# design.net
KiCad netlist of a schematic drawn in EasyEDA Pro
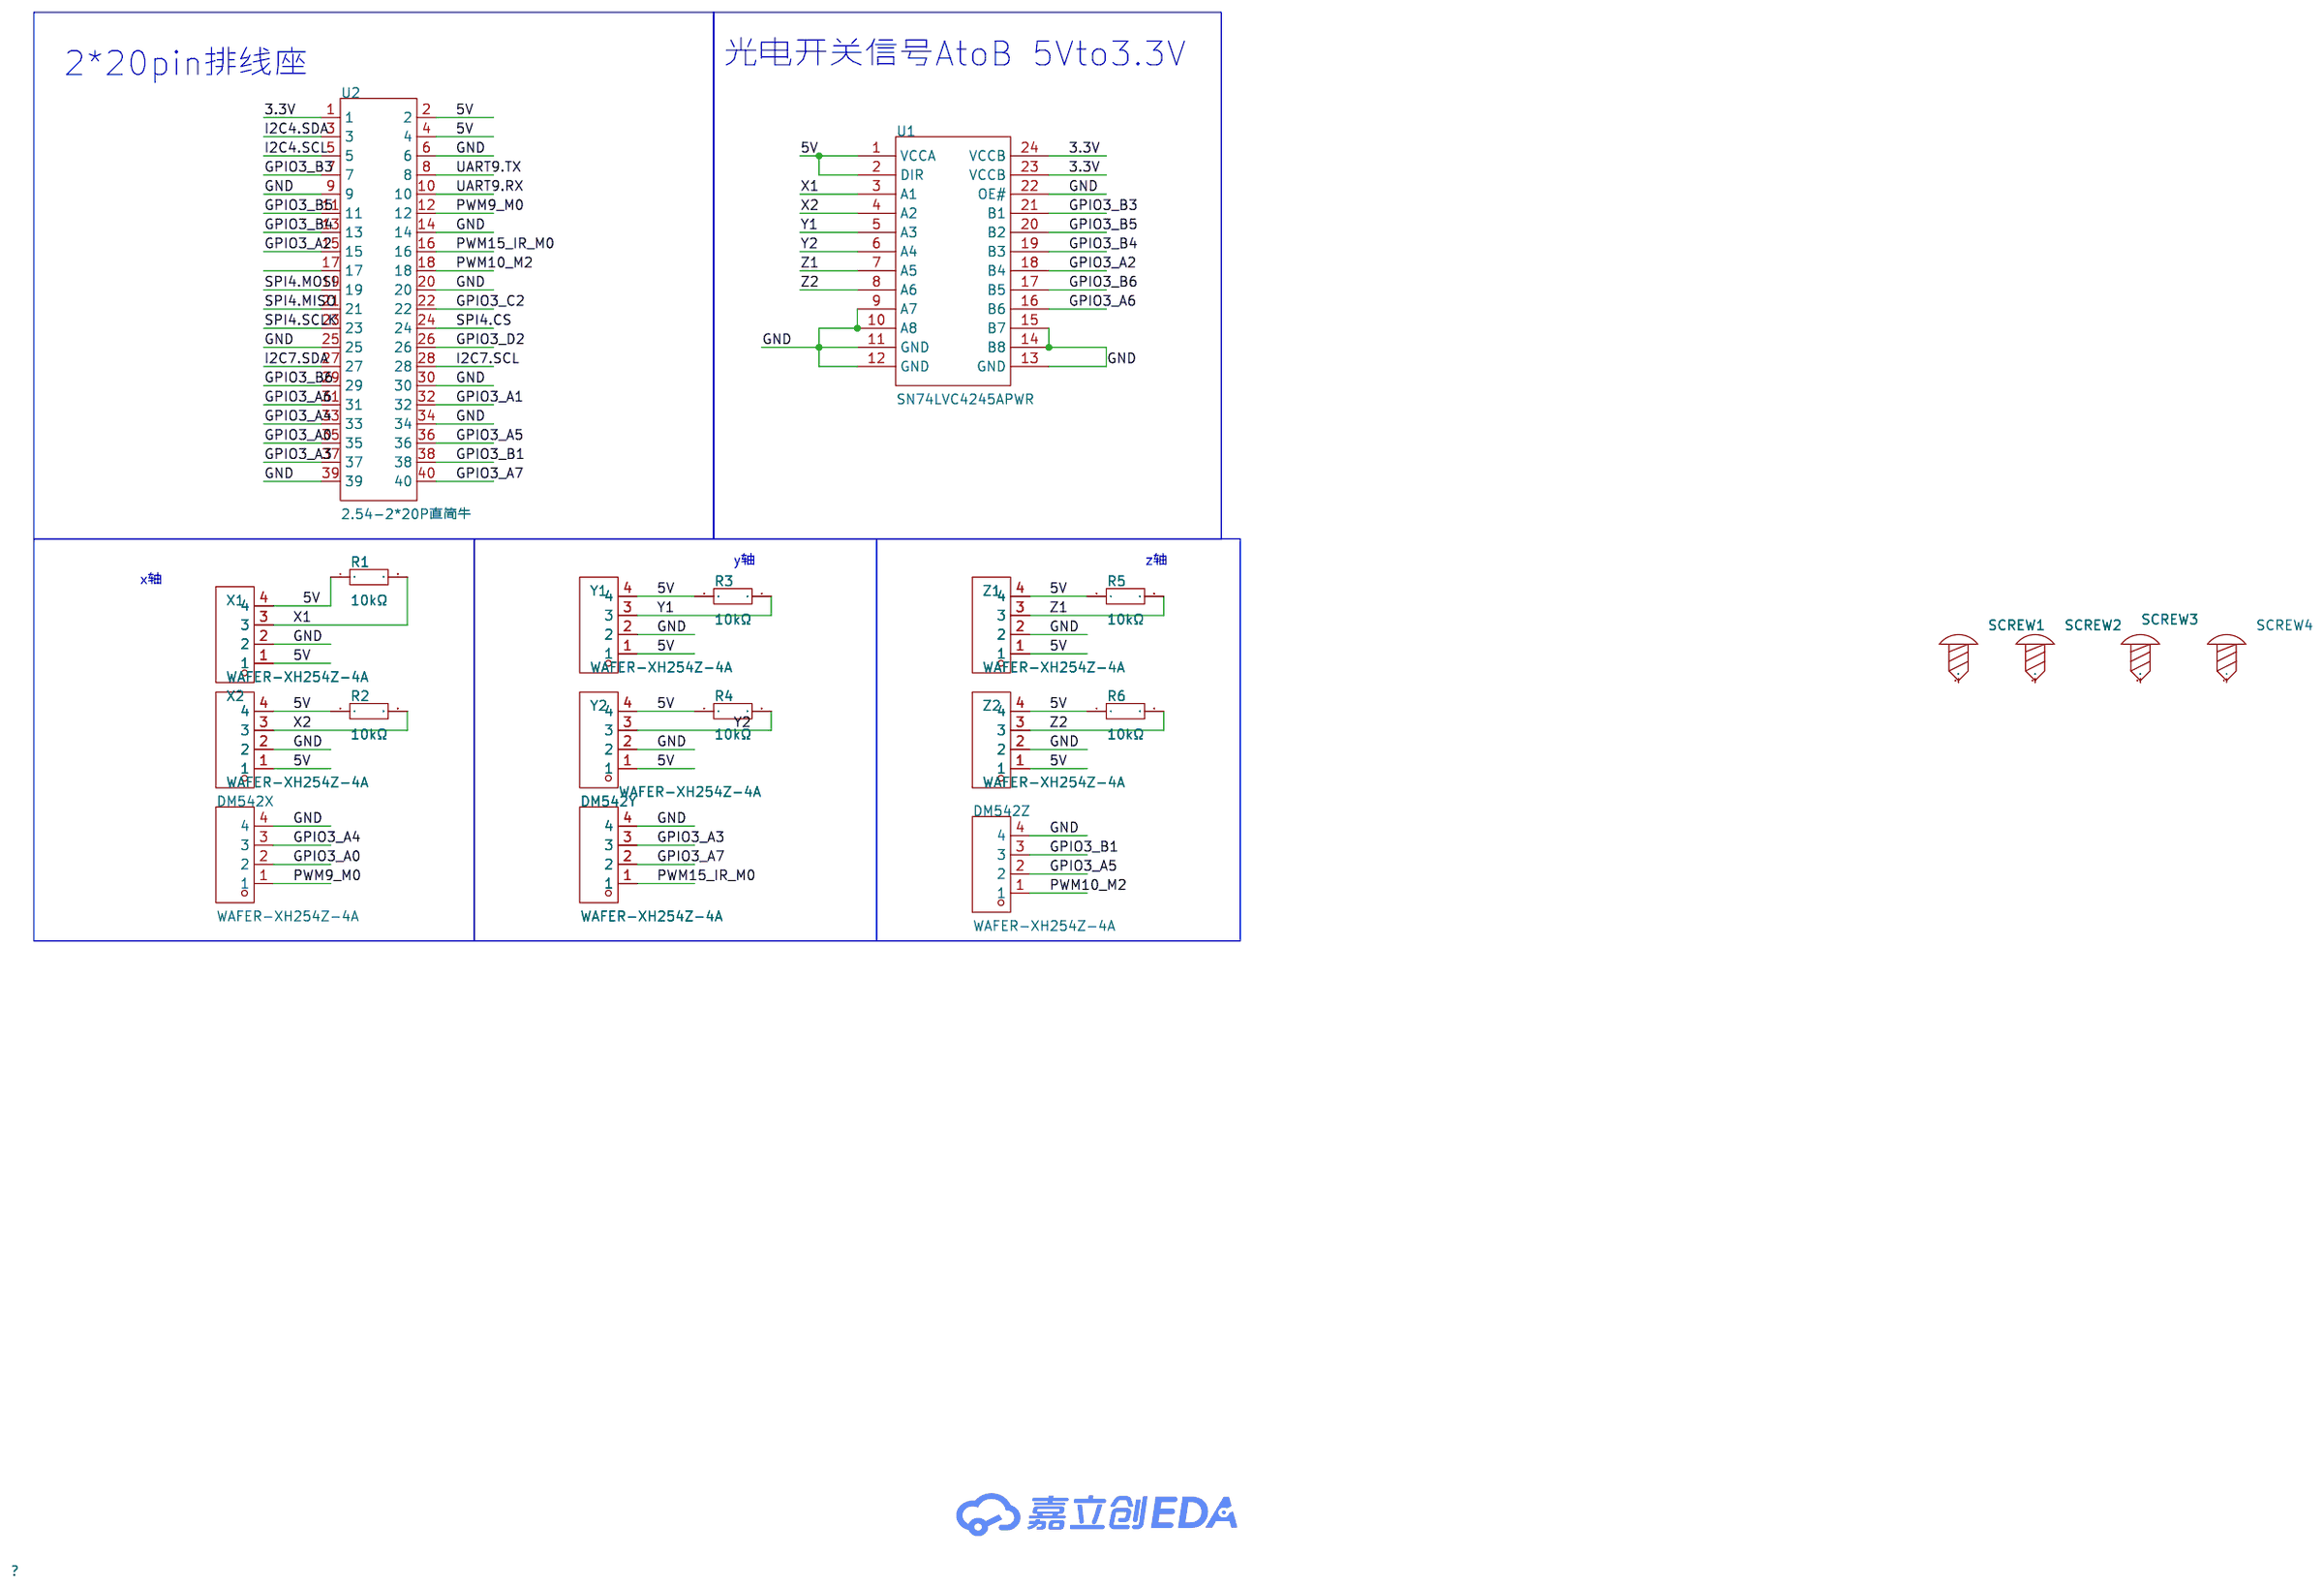
[diagram p0: schematic sheet]

(export (version "E")
  (design (tool "Eeschema 10.0.6"))
  (components
    (comp (ref "DM542X")
      (value "WAFER-XH254Z-4A")
      (footprint "easyedapro:CONN-TH_XH-4A")
      (description "插针结构:1x4P;间距:2.54mm;安装方式:直插;参考系列:XH;总PIN数:4P;排数:1;每排PIN数:4;额定电流:3A;触头材质:黄铜;工作温度:-25°C~+85°C;")
      (fields (field (name "Manufacturer") "HANBO(汉博)"))
      (libsource (lib "easyedapro") (part "WAFER-XH254Z-4A"))
    )
    (comp (ref "DM542Y")
      (value "WAFER-XH254Z-4A")
      (footprint "easyedapro:CONN-TH_XH-4A")
      (description "插针结构:1x4P;间距:2.54mm;安装方式:直插;参考系列:XH;总PIN数:4P;排数:1;每排PIN数:4;额定电流:3A;触头材质:黄铜;工作温度:-25°C~+85°C;")
      (fields (field (name "Manufacturer") "HANBO(汉博)"))
      (libsource (lib "easyedapro") (part "WAFER-XH254Z-4A"))
    )
    (comp (ref "DM542Z")
      (value "WAFER-XH254Z-4A")
      (footprint "easyedapro:CONN-TH_XH-4A")
      (description "插针结构:1x4P;间距:2.54mm;安装方式:直插;参考系列:XH;总PIN数:4P;排数:1;每排PIN数:4;额定电流:3A;触头材质:黄铜;工作温度:-25°C~+85°C;")
      (fields (field (name "Manufacturer") "HANBO(汉博)"))
      (libsource (lib "easyedapro") (part "WAFER-XH254Z-4A"))
    )
    (comp (ref "R1")
      (value "10kΩ")
      (footprint "easyedapro:R0603")
      (description "电阻类型:厚膜电阻;阻值:10kΩ;精度:±1%;功率:100mW;工作电压:75V;温度系数:±100ppm/°C;")
      (fields
        (field (name "Manufacturer Part") "0603WAF1002T5E")
        (field (name "Manufacturer") "UNI-ROYAL(厚声)")
      )
      (libsource (lib "easyedapro") (part "0603WAF1002T5E"))
    )
    (comp (ref "R2")
      (value "10kΩ")
      (footprint "easyedapro:R0603")
      (description "电阻类型:厚膜电阻;阻值:10kΩ;精度:±1%;功率:100mW;工作电压:75V;温度系数:±100ppm/°C;")
      (fields
        (field (name "Manufacturer Part") "0603WAF1002T5E")
        (field (name "Manufacturer") "UNI-ROYAL(厚声)")
      )
      (libsource (lib "easyedapro") (part "0603WAF1002T5E"))
    )
    (comp (ref "R3")
      (value "10kΩ")
      (footprint "easyedapro:R0603")
      (description "电阻类型:厚膜电阻;阻值:10kΩ;精度:±1%;功率:100mW;工作电压:75V;温度系数:±100ppm/°C;")
      (fields
        (field (name "Manufacturer Part") "0603WAF1002T5E")
        (field (name "Manufacturer") "UNI-ROYAL(厚声)")
      )
      (libsource (lib "easyedapro") (part "0603WAF1002T5E"))
    )
    (comp (ref "R4")
      (value "10kΩ")
      (footprint "easyedapro:R0603")
      (description "电阻类型:厚膜电阻;阻值:10kΩ;精度:±1%;功率:100mW;工作电压:75V;温度系数:±100ppm/°C;")
      (fields
        (field (name "Manufacturer Part") "0603WAF1002T5E")
        (field (name "Manufacturer") "UNI-ROYAL(厚声)")
      )
      (libsource (lib "easyedapro") (part "0603WAF1002T5E"))
    )
    (comp (ref "R5")
      (value "10kΩ")
      (footprint "easyedapro:R0603")
      (description "电阻类型:厚膜电阻;阻值:10kΩ;精度:±1%;功率:100mW;工作电压:75V;温度系数:±100ppm/°C;")
      (fields
        (field (name "Manufacturer Part") "0603WAF1002T5E")
        (field (name "Manufacturer") "UNI-ROYAL(厚声)")
      )
      (libsource (lib "easyedapro") (part "0603WAF1002T5E"))
    )
    (comp (ref "R6")
      (value "10kΩ")
      (footprint "easyedapro:R0603")
      (description "电阻类型:厚膜电阻;阻值:10kΩ;精度:±1%;功率:100mW;工作电压:75V;温度系数:±100ppm/°C;")
      (fields
        (field (name "Manufacturer Part") "0603WAF1002T5E")
        (field (name "Manufacturer") "UNI-ROYAL(厚声)")
      )
      (libsource (lib "easyedapro") (part "0603WAF1002T5E"))
    )
    (comp (ref "SCREW1")
      (value "~")
      (footprint "easyedapro:M3螺丝")
      (libsource (lib "easyedapro") (part "螺丝孔"))
    )
    (comp (ref "SCREW2")
      (value "~")
      (footprint "easyedapro:M3螺丝")
      (libsource (lib "easyedapro") (part "螺丝孔"))
    )
    (comp (ref "SCREW3")
      (value "~")
      (footprint "easyedapro:M3螺丝")
      (libsource (lib "easyedapro") (part "螺丝孔"))
    )
    (comp (ref "SCREW4")
      (value "~")
      (footprint "easyedapro:M3螺丝")
      (libsource (lib "easyedapro") (part "螺丝孔"))
    )
    (comp (ref "U1")
      (value "SN74LVC4245APWR")
      (footprint "easyedapro:TSSOP-24_L7.8-W4.4-P0.65-LS6.4-BL")
      (description "工作电压(VCCA):4.5V~5.5V;工作电压(VCCB):2.7V~3.6V;通道数:1;每个电路通道数:8;")
      (fields (field (name "Manufacturer") "TI(德州仪器)"))
      (libsource (lib "easyedapro") (part "SN74LVC4245APWR"))
    )
    (comp (ref "U2")
      (value "2.54-2*20P直简牛")
      (footprint "easyedapro:HDR-TH_40P-P2.54-V-M-R2-C20-S2.54")
      (description "插针结构:2x20P;间距:2.54mm;安装方式:直插;排数:双排;总PIN位数:40P;触头镀层:金;")
      (fields (field (name "Manufacturer") "BOOMELE(博穆精密)"))
      (libsource (lib "easyedapro") (part "PZ2.54-2*20"))
    )
    (comp (ref "X1")
      (value "WAFER-XH254Z-4A")
      (footprint "easyedapro:CONN-TH_XH-4A")
      (description "插针结构:1x4P;间距:2.54mm;安装方式:直插;参考系列:XH;总PIN数:4P;排数:1;每排PIN数:4;额定电流:3A;触头材质:黄铜;工作温度:-25°C~+85°C;")
      (fields (field (name "Manufacturer") "HANBO(汉博)"))
      (libsource (lib "easyedapro") (part "WAFER-XH254Z-4A"))
    )
    (comp (ref "X2")
      (value "WAFER-XH254Z-4A")
      (footprint "easyedapro:CONN-TH_XH-4A")
      (description "插针结构:1x4P;间距:2.54mm;安装方式:直插;参考系列:XH;总PIN数:4P;排数:1;每排PIN数:4;额定电流:3A;触头材质:黄铜;工作温度:-25°C~+85°C;")
      (fields (field (name "Manufacturer") "HANBO(汉博)"))
      (libsource (lib "easyedapro") (part "WAFER-XH254Z-4A"))
    )
    (comp (ref "Y1")
      (value "WAFER-XH254Z-4A")
      (footprint "easyedapro:CONN-TH_XH-4A")
      (description "插针结构:1x4P;间距:2.54mm;安装方式:直插;参考系列:XH;总PIN数:4P;排数:1;每排PIN数:4;额定电流:3A;触头材质:黄铜;工作温度:-25°C~+85°C;")
      (fields (field (name "Manufacturer") "HANBO(汉博)"))
      (libsource (lib "easyedapro") (part "WAFER-XH254Z-4A"))
    )
    (comp (ref "Y2")
      (value "WAFER-XH254Z-4A")
      (footprint "easyedapro:CONN-TH_XH-4A")
      (description "插针结构:1x4P;间距:2.54mm;安装方式:直插;参考系列:XH;总PIN数:4P;排数:1;每排PIN数:4;额定电流:3A;触头材质:黄铜;工作温度:-25°C~+85°C;")
      (fields (field (name "Manufacturer") "HANBO(汉博)"))
      (libsource (lib "easyedapro") (part "WAFER-XH254Z-4A"))
    )
    (comp (ref "Z1")
      (value "WAFER-XH254Z-4A")
      (footprint "easyedapro:CONN-TH_XH-4A")
      (description "插针结构:1x4P;间距:2.54mm;安装方式:直插;参考系列:XH;总PIN数:4P;排数:1;每排PIN数:4;额定电流:3A;触头材质:黄铜;工作温度:-25°C~+85°C;")
      (fields (field (name "Manufacturer") "HANBO(汉博)"))
      (libsource (lib "easyedapro") (part "WAFER-XH254Z-4A"))
    )
    (comp (ref "Z2")
      (value "WAFER-XH254Z-4A")
      (footprint "easyedapro:CONN-TH_XH-4A")
      (description "插针结构:1x4P;间距:2.54mm;安装方式:直插;参考系列:XH;总PIN数:4P;排数:1;每排PIN数:4;额定电流:3A;触头材质:黄铜;工作温度:-25°C~+85°C;")
      (fields (field (name "Manufacturer") "HANBO(汉博)"))
      (libsource (lib "easyedapro") (part "WAFER-XH254Z-4A"))
    )
  )
  (nets
    (net (code "1") (name "/3.3V") (class "Default")
      (node (ref "U1") (pin "23") (pinfunction "VCCB_23") (pintype "unspecified"))
      (node (ref "U1") (pin "24") (pinfunction "VCCB_24") (pintype "unspecified"))
      (node (ref "U2") (pin "1") (pinfunction "1_1") (pintype "unspecified"))
    )
    (net (code "2") (name "/5V") (class "Default")
      (node (ref "R1") (pin "1") (pinfunction "1_1") (pintype "input"))
      (node (ref "R2") (pin "1") (pinfunction "1_1") (pintype "input"))
      (node (ref "R3") (pin "1") (pinfunction "1_1") (pintype "input"))
      (node (ref "R4") (pin "1") (pinfunction "1_1") (pintype "input"))
      (node (ref "R5") (pin "1") (pinfunction "1_1") (pintype "input"))
      (node (ref "R6") (pin "1") (pinfunction "1_1") (pintype "input"))
      (node (ref "U1") (pin "1") (pinfunction "VCCA_1") (pintype "unspecified"))
      (node (ref "U1") (pin "2") (pinfunction "DIR_2") (pintype "unspecified"))
      (node (ref "U2") (pin "2") (pinfunction "2_2") (pintype "unspecified"))
      (node (ref "U2") (pin "4") (pinfunction "4_4") (pintype "unspecified"))
      (node (ref "X1") (pin "1") (pinfunction "1_1") (pintype "unspecified"))
      (node (ref "X1") (pin "4") (pinfunction "4_4") (pintype "unspecified"))
      (node (ref "X2") (pin "1") (pinfunction "1_1") (pintype "unspecified"))
      (node (ref "X2") (pin "4") (pinfunction "4_4") (pintype "unspecified"))
      (node (ref "Y1") (pin "1") (pinfunction "1_1") (pintype "unspecified"))
      (node (ref "Y1") (pin "4") (pinfunction "4_4") (pintype "unspecified"))
      (node (ref "Y2") (pin "1") (pinfunction "1_1") (pintype "unspecified"))
      (node (ref "Y2") (pin "4") (pinfunction "4_4") (pintype "unspecified"))
      (node (ref "Z1") (pin "1") (pinfunction "1_1") (pintype "unspecified"))
      (node (ref "Z1") (pin "4") (pinfunction "4_4") (pintype "unspecified"))
      (node (ref "Z2") (pin "1") (pinfunction "1_1") (pintype "unspecified"))
      (node (ref "Z2") (pin "4") (pinfunction "4_4") (pintype "unspecified"))
    )
    (net (code "3") (name "/GND") (class "Default")
      (node (ref "DM542X") (pin "4") (pinfunction "4_4") (pintype "unspecified"))
      (node (ref "DM542Y") (pin "4") (pinfunction "4_4") (pintype "unspecified"))
      (node (ref "DM542Z") (pin "4") (pinfunction "4_4") (pintype "unspecified"))
      (node (ref "U1") (pin "10") (pinfunction "A8_10") (pintype "unspecified"))
      (node (ref "U1") (pin "11") (pinfunction "GND_11") (pintype "unspecified"))
      (node (ref "U1") (pin "12") (pinfunction "GND_12") (pintype "unspecified"))
      (node (ref "U1") (pin "13") (pinfunction "GND_13") (pintype "unspecified"))
      (node (ref "U1") (pin "14") (pinfunction "B8_14") (pintype "unspecified"))
      (node (ref "U1") (pin "15") (pinfunction "B7_15") (pintype "unspecified"))
      (node (ref "U1") (pin "22") (pinfunction "OE#_22") (pintype "unspecified"))
      (node (ref "U1") (pin "9") (pinfunction "A7_9") (pintype "unspecified"))
      (node (ref "U2") (pin "14") (pinfunction "14_14") (pintype "unspecified"))
      (node (ref "U2") (pin "20") (pinfunction "20_20") (pintype "unspecified"))
      (node (ref "U2") (pin "25") (pinfunction "25_25") (pintype "unspecified"))
      (node (ref "U2") (pin "30") (pinfunction "30_30") (pintype "unspecified"))
      (node (ref "U2") (pin "34") (pinfunction "34_34") (pintype "unspecified"))
      (node (ref "U2") (pin "39") (pinfunction "39_39") (pintype "unspecified"))
      (node (ref "U2") (pin "6") (pinfunction "6_6") (pintype "unspecified"))
      (node (ref "U2") (pin "9") (pinfunction "9_9") (pintype "unspecified"))
      (node (ref "X1") (pin "2") (pinfunction "2_2") (pintype "unspecified"))
      (node (ref "X2") (pin "2") (pinfunction "2_2") (pintype "unspecified"))
      (node (ref "Y1") (pin "2") (pinfunction "2_2") (pintype "unspecified"))
      (node (ref "Y2") (pin "2") (pinfunction "2_2") (pintype "unspecified"))
      (node (ref "Z1") (pin "2") (pinfunction "2_2") (pintype "unspecified"))
      (node (ref "Z2") (pin "2") (pinfunction "2_2") (pintype "unspecified"))
    )
    (net (code "4") (name "/GPIO3_A0") (class "Default")
      (node (ref "DM542X") (pin "2") (pinfunction "2_2") (pintype "unspecified"))
      (node (ref "U2") (pin "35") (pinfunction "35_35") (pintype "unspecified"))
    )
    (net (code "5") (name "/GPIO3_A1") (class "Default")
      (node (ref "U2") (pin "32") (pinfunction "32_32") (pintype "unspecified"))
    )
    (net (code "6") (name "/GPIO3_A2") (class "Default")
      (node (ref "U1") (pin "18") (pinfunction "B4_18") (pintype "unspecified"))
      (node (ref "U2") (pin "15") (pinfunction "15_15") (pintype "unspecified"))
    )
    (net (code "7") (name "/GPIO3_A3") (class "Default")
      (node (ref "DM542Y") (pin "3") (pinfunction "3_3") (pintype "unspecified"))
      (node (ref "U2") (pin "37") (pinfunction "37_37") (pintype "unspecified"))
    )
    (net (code "8") (name "/GPIO3_A4") (class "Default")
      (node (ref "DM542X") (pin "3") (pinfunction "3_3") (pintype "unspecified"))
      (node (ref "U2") (pin "33") (pinfunction "33_33") (pintype "unspecified"))
    )
    (net (code "9") (name "/GPIO3_A5") (class "Default")
      (node (ref "DM542Z") (pin "2") (pinfunction "2_2") (pintype "unspecified"))
      (node (ref "U2") (pin "36") (pinfunction "36_36") (pintype "unspecified"))
    )
    (net (code "10") (name "/GPIO3_A6") (class "Default")
      (node (ref "U1") (pin "16") (pinfunction "B6_16") (pintype "unspecified"))
      (node (ref "U2") (pin "31") (pinfunction "31_31") (pintype "unspecified"))
    )
    (net (code "11") (name "/GPIO3_A7") (class "Default")
      (node (ref "DM542Y") (pin "2") (pinfunction "2_2") (pintype "unspecified"))
      (node (ref "U2") (pin "40") (pinfunction "40_40") (pintype "unspecified"))
    )
    (net (code "12") (name "/GPIO3_B1") (class "Default")
      (node (ref "DM542Z") (pin "3") (pinfunction "3_3") (pintype "unspecified"))
      (node (ref "U2") (pin "38") (pinfunction "38_38") (pintype "unspecified"))
    )
    (net (code "13") (name "/GPIO3_B3") (class "Default")
      (node (ref "U1") (pin "21") (pinfunction "B1_21") (pintype "unspecified"))
      (node (ref "U2") (pin "7") (pinfunction "7_7") (pintype "unspecified"))
    )
    (net (code "14") (name "/GPIO3_B4") (class "Default")
      (node (ref "U1") (pin "19") (pinfunction "B3_19") (pintype "unspecified"))
      (node (ref "U2") (pin "13") (pinfunction "13_13") (pintype "unspecified"))
    )
    (net (code "15") (name "/GPIO3_B5") (class "Default")
      (node (ref "U1") (pin "20") (pinfunction "B2_20") (pintype "unspecified"))
      (node (ref "U2") (pin "11") (pinfunction "11_11") (pintype "unspecified"))
    )
    (net (code "16") (name "/GPIO3_B6") (class "Default")
      (node (ref "U1") (pin "17") (pinfunction "B5_17") (pintype "unspecified"))
      (node (ref "U2") (pin "29") (pinfunction "29_29") (pintype "unspecified"))
    )
    (net (code "17") (name "/GPIO3_C2") (class "Default")
      (node (ref "U2") (pin "22") (pinfunction "22_22") (pintype "unspecified"))
    )
    (net (code "18") (name "/GPIO3_D2") (class "Default")
      (node (ref "U2") (pin "26") (pinfunction "26_26") (pintype "unspecified"))
    )
    (net (code "19") (name "/I2C4.SCL") (class "Default")
      (node (ref "U2") (pin "5") (pinfunction "5_5") (pintype "unspecified"))
    )
    (net (code "20") (name "/I2C4.SDA") (class "Default")
      (node (ref "U2") (pin "3") (pinfunction "3_3") (pintype "unspecified"))
    )
    (net (code "21") (name "/I2C7.SCL") (class "Default")
      (node (ref "U2") (pin "28") (pinfunction "28_28") (pintype "unspecified"))
    )
    (net (code "22") (name "/I2C7.SDA") (class "Default")
      (node (ref "U2") (pin "27") (pinfunction "27_27") (pintype "unspecified"))
    )
    (net (code "23") (name "/PWM9_M0") (class "Default")
      (node (ref "DM542X") (pin "1") (pinfunction "1_1") (pintype "unspecified"))
      (node (ref "U2") (pin "12") (pinfunction "12_12") (pintype "unspecified"))
    )
    (net (code "24") (name "/PWM10_M2") (class "Default")
      (node (ref "DM542Z") (pin "1") (pinfunction "1_1") (pintype "unspecified"))
      (node (ref "U2") (pin "18") (pinfunction "18_18") (pintype "unspecified"))
    )
    (net (code "25") (name "/PWM15_IR_M0") (class "Default")
      (node (ref "DM542Y") (pin "1") (pinfunction "1_1") (pintype "unspecified"))
      (node (ref "U2") (pin "16") (pinfunction "16_16") (pintype "unspecified"))
    )
    (net (code "26") (name "/SPI4.CS") (class "Default")
      (node (ref "U2") (pin "24") (pinfunction "24_24") (pintype "unspecified"))
    )
    (net (code "27") (name "/SPI4.MISO") (class "Default")
      (node (ref "U2") (pin "21") (pinfunction "21_21") (pintype "unspecified"))
    )
    (net (code "28") (name "/SPI4.MOSI") (class "Default")
      (node (ref "U2") (pin "19") (pinfunction "19_19") (pintype "unspecified"))
    )
    (net (code "29") (name "/SPI4.SCLK") (class "Default")
      (node (ref "U2") (pin "23") (pinfunction "23_23") (pintype "unspecified"))
    )
    (net (code "30") (name "/UART9.RX") (class "Default")
      (node (ref "U2") (pin "10") (pinfunction "10_10") (pintype "unspecified"))
    )
    (net (code "31") (name "/UART9.TX") (class "Default")
      (node (ref "U2") (pin "8") (pinfunction "8_8") (pintype "unspecified"))
    )
    (net (code "32") (name "/X1") (class "Default")
      (node (ref "R1") (pin "2") (pinfunction "2_2") (pintype "input"))
      (node (ref "U1") (pin "3") (pinfunction "A1_3") (pintype "unspecified"))
      (node (ref "X1") (pin "3") (pinfunction "3_3") (pintype "unspecified"))
    )
    (net (code "33") (name "/X2") (class "Default")
      (node (ref "R2") (pin "2") (pinfunction "2_2") (pintype "input"))
      (node (ref "U1") (pin "4") (pinfunction "A2_4") (pintype "unspecified"))
      (node (ref "X2") (pin "3") (pinfunction "3_3") (pintype "unspecified"))
    )
    (net (code "34") (name "/Y1") (class "Default")
      (node (ref "R3") (pin "2") (pinfunction "2_2") (pintype "input"))
      (node (ref "U1") (pin "5") (pinfunction "A3_5") (pintype "unspecified"))
      (node (ref "Y1") (pin "3") (pinfunction "3_3") (pintype "unspecified"))
    )
    (net (code "35") (name "/Y2") (class "Default")
      (node (ref "R4") (pin "2") (pinfunction "2_2") (pintype "input"))
      (node (ref "U1") (pin "6") (pinfunction "A4_6") (pintype "unspecified"))
      (node (ref "Y2") (pin "3") (pinfunction "3_3") (pintype "unspecified"))
    )
    (net (code "36") (name "/Z1") (class "Default")
      (node (ref "R5") (pin "2") (pinfunction "2_2") (pintype "input"))
      (node (ref "U1") (pin "7") (pinfunction "A5_7") (pintype "unspecified"))
      (node (ref "Z1") (pin "3") (pinfunction "3_3") (pintype "unspecified"))
    )
    (net (code "37") (name "/Z2") (class "Default")
      (node (ref "R6") (pin "2") (pinfunction "2_2") (pintype "input"))
      (node (ref "U1") (pin "8") (pinfunction "A6_8") (pintype "unspecified"))
      (node (ref "Z2") (pin "3") (pinfunction "3_3") (pintype "unspecified"))
    )
    (net (code "38") (name "unconnected-(SCREW1-Pad1)") (class "Default")
      (node (ref "SCREW1") (pin "1") (pinfunction "1_1") (pintype "input"))
    )
    (net (code "39") (name "unconnected-(SCREW2-Pad1)") (class "Default")
      (node (ref "SCREW2") (pin "1") (pinfunction "1_1") (pintype "input"))
    )
    (net (code "40") (name "unconnected-(SCREW3-Pad1)") (class "Default")
      (node (ref "SCREW3") (pin "1") (pinfunction "1_1") (pintype "input"))
    )
    (net (code "41") (name "unconnected-(SCREW4-Pad1)") (class "Default")
      (node (ref "SCREW4") (pin "1") (pinfunction "1_1") (pintype "input"))
    )
    (net (code "42") (name "unconnected-(U2-Pad17)") (class "Default")
      (node (ref "U2") (pin "17") (pinfunction "17_17") (pintype "unspecified"))
    )
  )
)
